# Elreg_Sender_Power.net
KiCad netlist of a schematic drawn in Altium Designer
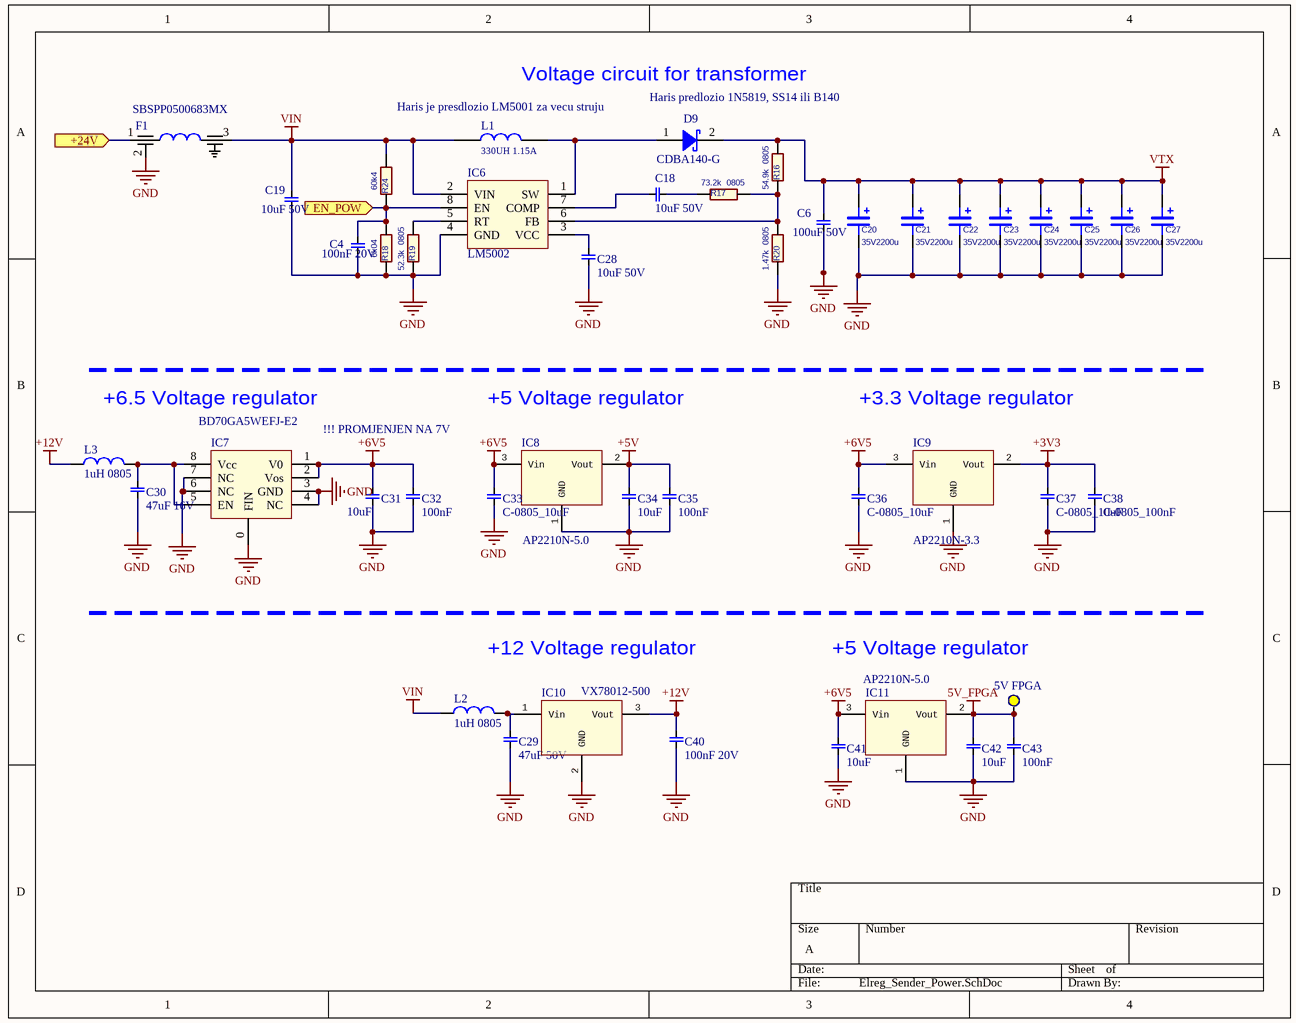
[diagram p0: Elreg_Sender_Power.SchDoc]

(export (version "E")
  (design (tool "Eeschema 10.0.6"))
  (components
    (comp (ref "C4")
      (value "100nF 20V")
      (footprint "C-0603")
      (fields (field (name "TOLERANCE") "±10%"))
      (libsource (lib "Elreg_Sender") (part "C-0805_100nF"))
    )
    (comp (ref "C6")
      (value "100uF 50V")
      (footprint "C-0805")
      (fields (field (name "TOLERANCE") "±10%"))
      (libsource (lib "Elreg_Sender") (part "C-0805_10uF"))
    )
    (comp (ref "C18")
      (value "10uF 50V")
      (footprint "C-0603")
      (fields (field (name "TOLERANCE") "±10%"))
      (libsource (lib "Elreg_Sender") (part "C-0805_10uF"))
    )
    (comp (ref "C19")
      (value "10uF 50V")
      (footprint "C-0805")
      (fields (field (name "TOLERANCE") "±10%"))
      (libsource (lib "Elreg_Sender") (part "C-0805_10uF"))
    )
    (comp (ref "C20")
      (value "35V2200u")
      (footprint "CAP_16X25")
      (description "Capacitor")
      (fields
        (field (name "MANUFACTURER") "Kemet")
        (field (name "MANUFACTURER PART NUMBER") "ESH228M035AM7AA")
      )
      (libsource (lib "Elreg_Sender") (part "CAP_2200uF_35V"))
    )
    (comp (ref "C21")
      (value "35V2200u")
      (footprint "CAP_16X25")
      (description "Capacitor")
      (fields
        (field (name "MANUFACTURER") "Kemet")
        (field (name "MANUFACTURER PART NUMBER") "ESH228M035AM7AA")
      )
      (libsource (lib "Elreg_Sender") (part "CAP_2200uF_35V"))
    )
    (comp (ref "C22")
      (value "35V2200u")
      (footprint "CAP_16X25")
      (description "Capacitor")
      (fields
        (field (name "MANUFACTURER") "Kemet")
        (field (name "MANUFACTURER PART NUMBER") "ESH228M035AM7AA")
      )
      (libsource (lib "Elreg_Sender") (part "CAP_2200uF_35V"))
    )
    (comp (ref "C23")
      (value "35V2200u")
      (footprint "CAP_16X25")
      (description "Capacitor")
      (fields
        (field (name "MANUFACTURER") "Kemet")
        (field (name "MANUFACTURER PART NUMBER") "ESH228M035AM7AA")
      )
      (libsource (lib "Elreg_Sender") (part "CAP_2200uF_35V"))
    )
    (comp (ref "C24")
      (value "35V2200u")
      (footprint "CAP_16X25")
      (description "Capacitor")
      (fields
        (field (name "MANUFACTURER") "Kemet")
        (field (name "MANUFACTURER PART NUMBER") "ESH228M035AM7AA")
      )
      (libsource (lib "Elreg_Sender") (part "CAP_2200uF_35V"))
    )
    (comp (ref "C25")
      (value "35V2200u")
      (footprint "CAP_16X25")
      (description "Capacitor")
      (fields
        (field (name "MANUFACTURER") "Kemet")
        (field (name "MANUFACTURER PART NUMBER") "ESH228M035AM7AA")
      )
      (libsource (lib "Elreg_Sender") (part "CAP_2200uF_35V"))
    )
    (comp (ref "C26")
      (value "35V2200u")
      (footprint "CAP_16X25")
      (description "Capacitor")
      (fields
        (field (name "MANUFACTURER") "Kemet")
        (field (name "MANUFACTURER PART NUMBER") "ESH228M035AM7AA")
      )
      (libsource (lib "Elreg_Sender") (part "CAP_2200uF_35V"))
    )
    (comp (ref "C27")
      (value "35V2200u")
      (footprint "CAP_16X25")
      (description "Capacitor")
      (fields
        (field (name "MANUFACTURER") "Kemet")
        (field (name "MANUFACTURER PART NUMBER") "ESH228M035AM7AA")
      )
      (libsource (lib "Elreg_Sender") (part "CAP_2200uF_35V"))
    )
    (comp (ref "C28")
      (value "10uF 50V")
      (footprint "C-0603")
      (fields (field (name "TOLERANCE") "±10%"))
      (libsource (lib "Elreg_Sender") (part "C-0805_10uF"))
    )
    (comp (ref "C29")
      (value "47uF 50V")
      (footprint "C-0603")
      (fields (field (name "TOLERANCE") "±10%"))
      (libsource (lib "Elreg_Sender") (part "C-0805_10uF"))
    )
    (comp (ref "C30")
      (value "47uF 16V")
      (footprint "C-0603")
      (fields (field (name "TOLERANCE") "±10%"))
      (libsource (lib "Elreg_Sender") (part "C-0805_3_3uF"))
    )
    (comp (ref "C31")
      (value "10uF")
      (footprint "C-0603")
      (fields (field (name "TOLERANCE") "±10%"))
      (libsource (lib "Elreg_Sender") (part "C-0805_10uF"))
    )
    (comp (ref "C32")
      (value "100nF")
      (footprint "C-0603")
      (fields (field (name "TOLERANCE") "±10%"))
      (libsource (lib "Elreg_Sender") (part "C-0805_100nF"))
    )
    (comp (ref "C33")
      (value "C-0805_10uF")
      (footprint "C-0603")
      (fields (field (name "TOLERANCE") "±10%"))
      (libsource (lib "Elreg_Sender") (part "C-0805_10uF"))
    )
    (comp (ref "C34")
      (value "10uF")
      (footprint "C-0603")
      (fields (field (name "TOLERANCE") "±10%"))
      (libsource (lib "Elreg_Sender") (part "C-0805_10uF"))
    )
    (comp (ref "C35")
      (value "100nF")
      (footprint "C-0603")
      (fields (field (name "TOLERANCE") "±10%"))
      (libsource (lib "Elreg_Sender") (part "C-0805_100nF"))
    )
    (comp (ref "C36")
      (value "C-0805_10uF")
      (footprint "C-0805")
      (fields (field (name "TOLERANCE") "±10%"))
      (libsource (lib "Elreg_Sender") (part "C-0805_10uF"))
    )
    (comp (ref "C37")
      (value "C-0805_10uF")
      (footprint "C-0805")
      (fields (field (name "TOLERANCE") "±10%"))
      (libsource (lib "Elreg_Sender") (part "C-0805_10uF"))
    )
    (comp (ref "C38")
      (value "C-0805_100nF")
      (footprint "C-0805")
      (fields (field (name "TOLERANCE") "±10%"))
      (libsource (lib "Elreg_Sender") (part "C-0805_100nF"))
    )
    (comp (ref "C40")
      (value "100nF 20V")
      (footprint "C-0805")
      (fields (field (name "TOLERANCE") "±10%"))
      (libsource (lib "Elreg_Sender") (part "C-0805_100nF"))
    )
    (comp (ref "C41")
      (value "10uF")
      (footprint "C-0603")
      (fields (field (name "TOLERANCE") "±10%"))
      (libsource (lib "Elreg_Sender") (part "C-0805_10uF"))
    )
    (comp (ref "C42")
      (value "10uF")
      (footprint "C-0603")
      (fields (field (name "TOLERANCE") "±10%"))
      (libsource (lib "Elreg_Sender") (part "C-0805_10uF"))
    )
    (comp (ref "C43")
      (value "100nF")
      (footprint "C-0603")
      (fields (field (name "TOLERANCE") "±10%"))
      (libsource (lib "Elreg_Sender") (part "C-0805_100nF"))
    )
    (comp (ref "D9")
      (value "DIODE SCHOTTKY 40V 1A DO214AC")
      (footprint "DFN380P520X45-2N")
      (fields
        (field (name "MANUFACTURER PART NUMBER 1") "CDBA140-G")
        (field (name "BASE PART NUMBER") "CDBA140")
      )
      (libsource (lib "Elreg_Sender") (part "DIODE SCHOTTKY 40V 1A DO214AC"))
    )
    (comp (ref "F1")
      (value "SBSPP0500683MX")
      (footprint "Filter_SBSPP0500")
      (libsource (lib "Elreg_Sender") (part "Filter_SBSPP0500683MX"))
    )
    (comp (ref "IC6")
      (value "LM5002")
      (footprint "SOIC127P600X205-8N")
      (fields (field (name "BASE PART NUMBER") "LM5002"))
      (libsource (lib "Elreg_Sender") (part "LM5002"))
    )
    (comp (ref "IC7")
      (value "BD70GA5WEFJ-E2")
      (footprint "HTSOP-J8")
      (libsource (lib "Elreg_Sender") (part "BD70GA5WEFJ-E2"))
    )
    (comp (ref "IC8")
      (value "AP2210N-5.0")
      (footprint "SOT23-3")
      (description "AP2210N-5.0TRG1DICT-ND")
      (libsource (lib "Elreg_Sender") (part "AP2210N-5"))
    )
    (comp (ref "IC9")
      (value "AP2210N-3.3")
      (footprint "SOT23-3")
      (description "AP2210N-3.3TRG1DICT-ND")
      (libsource (lib "Elreg_Sender") (part "AP2210N-3.3"))
    )
    (comp (ref "IC10")
      (value "VX78012-500")
      (footprint "VREG")
      (libsource (lib "Elreg_Sender") (part "VX78012-500"))
    )
    (comp (ref "IC11")
      (value "AP2210N-5.0")
      (footprint "SOT23-3")
      (description "AP2210N-5.0TRG1DICT-ND")
      (libsource (lib "Elreg_Sender") (part "AP2210N-5"))
    )
    (comp (ref "L1")
      (value "330UH 1.15A")
      (footprint "IND")
      (libsource (lib "Elreg_Sender") (part "FIXED IND 330UH 1.15A 580 MOHM"))
    )
    (comp (ref "L2")
      (value "1uH 0805")
      (footprint "0805")
      (libsource (lib "Elreg_Sender") (part "induktor_0806"))
    )
    (comp (ref "L3")
      (value "1uH 0805")
      (footprint "0805")
      (libsource (lib "Elreg_Sender") (part "induktor_0806"))
    )
    (comp (ref "R16")
      (value "54.9k  0805")
      (footprint "R-0603")
      (description "RES xx OHM 1/8W 5% 0805 SMD")
      (libsource (lib "Elreg (Skipper)") (part "CRCW0805xxxxJN Default"))
    )
    (comp (ref "R17")
      (value "73.2k  0805")
      (footprint "R-0603")
      (description "RES xx OHM 1/8W 5% 0805 SMD")
      (libsource (lib "") (part "CRCW0805xxxxJN Default_1"))
    )
    (comp (ref "R18")
      (value "6k04")
      (footprint "R-0603")
      (description "RES 1 KOHM 1/8W 1% 0805 SMD")
      (fields (field (name "TOLERANCE") "±1%"))
      (libsource (lib "Elreg (Skipper)") (part "CRCW08051K00FKEA"))
    )
    (comp (ref "R19")
      (value "52.3k  0805")
      (footprint "R-0603")
      (description "RES xx OHM 1/8W 5% 0805 SMD")
      (libsource (lib "Elreg (Skipper)") (part "CRCW0805xxxxJN Default"))
    )
    (comp (ref "R20")
      (value "1.47k  0805")
      (footprint "R-0603")
      (description "RES xx OHM 1/8W 5% 0805 SMD")
      (libsource (lib "Elreg (Skipper)") (part "CRCW0805xxxxJN Default"))
    )
    (comp (ref "R24")
      (value "60k4")
      (footprint "R-0603")
      (description "RES 1 KOHM 1/8W 1% 0805 SMD")
      (fields (field (name "TOLERANCE") "±1%"))
      (libsource (lib "Elreg (Skipper)") (part "CRCW08051K00FKEA"))
    )
    (comp (ref "TP5")
      (value "5V FPGA")
      (footprint "Test_Point")
      (libsource (lib "Elreg_Sender") (part "Test_Point"))
    )
  )
  (nets
    (net (code "1") (name "+3V3") (class "Default")
      (node (ref "C37") (pin "1") (pinfunction "G_1") (pintype "passive"))
      (node (ref "C38") (pin "2") (pinfunction "G_2") (pintype "passive"))
      (node (ref "IC9") (pin "2") (pinfunction "Vout_2") (pintype "passive"))
    )
    (net (code "2") (name "+5V") (class "Default")
      (node (ref "C34") (pin "1") (pinfunction "G_1") (pintype "passive"))
      (node (ref "C35") (pin "2") (pinfunction "G_2") (pintype "passive"))
      (node (ref "IC8") (pin "2") (pinfunction "Vout_2") (pintype "passive"))
    )
    (net (code "3") (name "+6V5") (class "Default")
      (node (ref "C31") (pin "1") (pinfunction "G_1") (pintype "passive"))
      (node (ref "C32") (pin "2") (pinfunction "G_2") (pintype "passive"))
      (node (ref "C33") (pin "1") (pinfunction "G_1") (pintype "passive"))
      (node (ref "C36") (pin "1") (pinfunction "G_1") (pintype "passive"))
      (node (ref "C41") (pin "1") (pinfunction "G_1") (pintype "passive"))
      (node (ref "IC11") (pin "3") (pinfunction "Vin_3") (pintype "passive"))
      (node (ref "IC7") (pin "1") (pinfunction "V0_1") (pintype "passive"))
      (node (ref "IC7") (pin "2") (pinfunction "Vos_2") (pintype "passive"))
      (node (ref "IC8") (pin "3") (pinfunction "Vin_3") (pintype "passive"))
      (node (ref "IC9") (pin "3") (pinfunction "Vin_3") (pintype "passive"))
    )
    (net (code "4") (name "+12V") (class "Default")
      (node (ref "C40") (pin "2") (pinfunction "G_2") (pintype "passive"))
      (node (ref "IC10") (pin "3") (pinfunction "Vout_3") (pintype "passive"))
      (node (ref "L3") (pin "1") (pinfunction "A_1") (pintype "passive"))
    )
    (net (code "5") (name "/+24V") (class "Default")
      (node (ref "F1") (pin "1") (pinfunction "1_1") (pintype "passive"))
    )
    (net (code "6") (name "/EN_POW") (class "Default")
      (node (ref "C4") (pin "2") (pinfunction "G_2") (pintype "passive"))
      (node (ref "IC6") (pin "8") (pinfunction "EN_8") (pintype "passive"))
      (node (ref "R18") (pin "2") (pinfunction "2_2") (pintype "passive"))
      (node (ref "R24") (pin "1") (pinfunction "1_1") (pintype "passive"))
    )
    (net (code "7") (name "5V_FPGA") (class "Default")
      (node (ref "C42") (pin "1") (pinfunction "G_1") (pintype "passive"))
      (node (ref "C43") (pin "2") (pinfunction "G_2") (pintype "passive"))
      (node (ref "IC11") (pin "2") (pinfunction "Vout_2") (pintype "passive"))
      (node (ref "TP5") (pin "1") (pinfunction "1_1") (pintype "passive"))
    )
    (net (code "8") (name "GND") (class "Default")
      (node (ref "C19") (pin "2") (pinfunction "G_2") (pintype "passive"))
      (node (ref "C20") (pin "2") (pinfunction "2_2") (pintype "passive"))
      (node (ref "C21") (pin "2") (pinfunction "2_2") (pintype "passive"))
      (node (ref "C22") (pin "2") (pinfunction "2_2") (pintype "passive"))
      (node (ref "C23") (pin "2") (pinfunction "2_2") (pintype "passive"))
      (node (ref "C24") (pin "2") (pinfunction "2_2") (pintype "passive"))
      (node (ref "C25") (pin "2") (pinfunction "2_2") (pintype "passive"))
      (node (ref "C26") (pin "2") (pinfunction "2_2") (pintype "passive"))
      (node (ref "C27") (pin "2") (pinfunction "2_2") (pintype "passive"))
      (node (ref "C28") (pin "2") (pinfunction "G_2") (pintype "passive"))
      (node (ref "C29") (pin "2") (pinfunction "G_2") (pintype "passive"))
      (node (ref "C30") (pin "1") (pinfunction "G_1") (pintype "passive"))
      (node (ref "C31") (pin "2") (pinfunction "G_2") (pintype "passive"))
      (node (ref "C32") (pin "1") (pinfunction "G_1") (pintype "passive"))
      (node (ref "C33") (pin "2") (pinfunction "G_2") (pintype "passive"))
      (node (ref "C34") (pin "2") (pinfunction "G_2") (pintype "passive"))
      (node (ref "C35") (pin "1") (pinfunction "G_1") (pintype "passive"))
      (node (ref "C36") (pin "2") (pinfunction "G_2") (pintype "passive"))
      (node (ref "C37") (pin "2") (pinfunction "G_2") (pintype "passive"))
      (node (ref "C38") (pin "1") (pinfunction "G_1") (pintype "passive"))
      (node (ref "C4") (pin "1") (pinfunction "G_1") (pintype "passive"))
      (node (ref "C40") (pin "1") (pinfunction "G_1") (pintype "passive"))
      (node (ref "C41") (pin "2") (pinfunction "G_2") (pintype "passive"))
      (node (ref "C42") (pin "2") (pinfunction "G_2") (pintype "passive"))
      (node (ref "C43") (pin "1") (pinfunction "G_1") (pintype "passive"))
      (node (ref "C6") (pin "2") (pinfunction "G_2") (pintype "passive"))
      (node (ref "F1") (pin "2") (pinfunction "2_2") (pintype "passive"))
      (node (ref "IC10") (pin "2") (pinfunction "GND_2") (pintype "passive"))
      (node (ref "IC11") (pin "1") (pinfunction "GND_1") (pintype "passive"))
      (node (ref "IC6") (pin "4") (pinfunction "GND_4") (pintype "passive"))
      (node (ref "IC7") (pin "0") (pinfunction "FIN_0") (pintype "passive"))
      (node (ref "IC7") (pin "3") (pinfunction "GND_3") (pintype "passive"))
      (node (ref "IC7") (pin "4") (pinfunction "NC_4") (pintype "passive"))
      (node (ref "IC7") (pin "6") (pinfunction "NC_6") (pintype "passive"))
      (node (ref "IC7") (pin "7") (pinfunction "NC_7") (pintype "passive"))
      (node (ref "IC8") (pin "1") (pinfunction "GND_1") (pintype "passive"))
      (node (ref "IC9") (pin "1") (pinfunction "GND_1") (pintype "passive"))
      (node (ref "R18") (pin "1") (pinfunction "1_1") (pintype "passive"))
      (node (ref "R19") (pin "1") (pinfunction "1_1") (pintype "passive"))
      (node (ref "R20") (pin "1") (pinfunction "1_1") (pintype "passive"))
    )
    (net (code "9") (name "Net-(C18-G-Pad2)") (class "Default")
      (node (ref "C18") (pin "2") (pinfunction "G_2") (pintype "passive"))
      (node (ref "R17") (pin "1") (pinfunction "1_1") (pintype "passive"))
    )
    (net (code "10") (name "Net-(IC6-COMP)") (class "Default")
      (node (ref "C18") (pin "1") (pinfunction "G_1") (pintype "passive"))
      (node (ref "IC6") (pin "7") (pinfunction "COMP_7") (pintype "passive"))
    )
    (net (code "11") (name "Net-(IC6-FB)") (class "Default")
      (node (ref "IC6") (pin "6") (pinfunction "FB_6") (pintype "passive"))
      (node (ref "R16") (pin "1") (pinfunction "1_1") (pintype "passive"))
      (node (ref "R17") (pin "2") (pinfunction "2_2") (pintype "passive"))
      (node (ref "R20") (pin "2") (pinfunction "2_2") (pintype "passive"))
    )
    (net (code "12") (name "Net-(IC6-RT)") (class "Default")
      (node (ref "IC6") (pin "5") (pinfunction "RT_5") (pintype "passive"))
      (node (ref "R19") (pin "2") (pinfunction "2_2") (pintype "passive"))
    )
    (net (code "13") (name "Net-(IC6-SW)") (class "Default")
      (node (ref "D9") (pin "1") (pinfunction "A_1") (pintype "passive"))
      (node (ref "IC6") (pin "1") (pinfunction "SW_1") (pintype "passive"))
      (node (ref "L1") (pin "2") (pinfunction "A_2") (pintype "passive"))
    )
    (net (code "14") (name "Net-(IC6-VCC)") (class "Default")
      (node (ref "C28") (pin "1") (pinfunction "G_1") (pintype "passive"))
      (node (ref "IC6") (pin "3") (pinfunction "VCC_3") (pintype "passive"))
    )
    (net (code "15") (name "Net-(IC7-EN)") (class "Default")
      (node (ref "C30") (pin "2") (pinfunction "G_2") (pintype "passive"))
      (node (ref "IC7") (pin "5") (pinfunction "EN_5") (pintype "passive"))
      (node (ref "IC7") (pin "8") (pinfunction "Vcc_8") (pintype "passive"))
      (node (ref "L3") (pin "2") (pinfunction "A_2") (pintype "passive"))
    )
    (net (code "16") (name "Net-(IC10-Vin)") (class "Default")
      (node (ref "C29") (pin "1") (pinfunction "G_1") (pintype "passive"))
      (node (ref "IC10") (pin "1") (pinfunction "Vin_1") (pintype "passive"))
      (node (ref "L2") (pin "2") (pinfunction "A_2") (pintype "passive"))
    )
    (net (code "17") (name "VIN") (class "Default")
      (node (ref "C19") (pin "1") (pinfunction "G_1") (pintype "passive"))
      (node (ref "F1") (pin "3") (pinfunction "3_3") (pintype "passive"))
      (node (ref "IC6") (pin "2") (pinfunction "VIN_2") (pintype "passive"))
      (node (ref "L1") (pin "1") (pinfunction "A_1") (pintype "passive"))
      (node (ref "L2") (pin "1") (pinfunction "A_1") (pintype "passive"))
      (node (ref "R24") (pin "2") (pinfunction "2_2") (pintype "passive"))
    )
    (net (code "18") (name "VTX") (class "Default")
      (node (ref "C20") (pin "1") (pinfunction "1_1") (pintype "passive"))
      (node (ref "C21") (pin "1") (pinfunction "1_1") (pintype "passive"))
      (node (ref "C22") (pin "1") (pinfunction "1_1") (pintype "passive"))
      (node (ref "C23") (pin "1") (pinfunction "1_1") (pintype "passive"))
      (node (ref "C24") (pin "1") (pinfunction "1_1") (pintype "passive"))
      (node (ref "C25") (pin "1") (pinfunction "1_1") (pintype "passive"))
      (node (ref "C26") (pin "1") (pinfunction "1_1") (pintype "passive"))
      (node (ref "C27") (pin "1") (pinfunction "1_1") (pintype "passive"))
      (node (ref "C6") (pin "1") (pinfunction "G_1") (pintype "passive"))
      (node (ref "D9") (pin "2") (pinfunction "A_2") (pintype "passive"))
      (node (ref "R16") (pin "2") (pinfunction "2_2") (pintype "passive"))
    )
  )
)
